# CTRL.net
KiCad netlist of a schematic drawn in Altium Designer
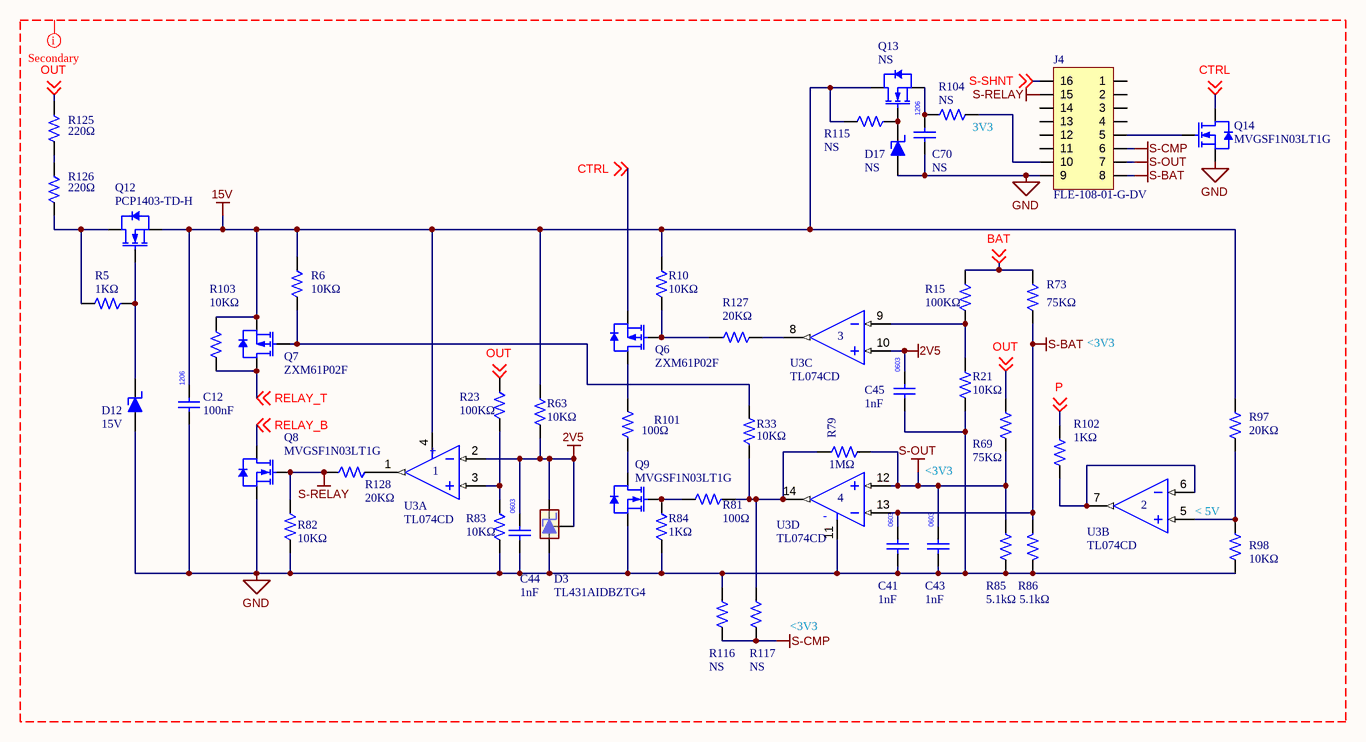
[diagram p0: CTRL.SchDoc]

(export (version "E")
  (design (tool "Eeschema 10.0.6"))
  (components
    (comp (ref "C12")
      (value "100nF")
      (footprint "CC/NM 1206")
      (libsource (lib "Capacitors_1206") (part "Capacitor 100nF"))
    )
    (comp (ref "C41")
      (value "1nF")
      (footprint "CC/NM 0603")
      (libsource (lib "Capacitors_0603") (part "Capacitor 1nF"))
    )
    (comp (ref "C43")
      (value "1nF")
      (footprint "CC/NM 0603")
      (libsource (lib "Capacitors_0603") (part "Capacitor 1nF"))
    )
    (comp (ref "C44")
      (value "1nF")
      (footprint "CC/NM 0603")
      (libsource (lib "Capacitors_0603") (part "Capacitor 1nF"))
    )
    (comp (ref "C45")
      (value "1nF")
      (footprint "CC/NM 0603")
      (libsource (lib "Capacitors_0603") (part "Capacitor 1nF"))
    )
    (comp (ref "C70")
      (value "NS")
      (footprint "CC/NM 1206")
      (description "100nF")
      (libsource (lib "Capacitors_1206") (part "Capacitor 100nF"))
    )
    (comp (ref "D3")
      (value "TL431AIDBZTG4")
      (footprint "SOT95P237X112-3N")
      (description "TL43xx Precision Programmable Reference")
      (libsource (lib "Charger") (part "TL431AIDBZTG4"))
    )
    (comp (ref "D12")
      (value "15V")
      (footprint "SOT95P237X112-3N")
      (libsource (lib "Charger") (part "Zener_18V"))
    )
    (comp (ref "D17")
      (value "NS")
      (footprint "SOT95P237X112-3N")
      (libsource (lib "Charger") (part "Zener_18V"))
    )
    (comp (ref "J4")
      (value "FLE-108-01-G-DV")
      (footprint "FLE-108-01-G-DV")
      (libsource (lib "Charger") (part "FLE-108-01-G-DV"))
    )
    (comp (ref "Q6")
      (value "ZXM61P02F")
      (footprint "SOT95P237X112-3N")
      (description "PMOS  -20V 0.9A 600 mohm")
      (libsource (lib "Charger") (part "ZXM61P02F"))
    )
    (comp (ref "Q7")
      (value "ZXM61P02F")
      (footprint "SOT95P237X112-3N")
      (description "PMOS  -20V 0.9A 600 mohm")
      (libsource (lib "Charger") (part "ZXM61P02F"))
    )
    (comp (ref "Q8")
      (value "MVGSF1N03LT1G")
      (footprint "SOT95P237X112-3N")
      (description "NMOS 30V 2.1A  80mR")
      (libsource (lib "Charger") (part "MVGSF1N03LT1G"))
    )
    (comp (ref "Q9")
      (value "MVGSF1N03LT1G")
      (footprint "SOT95P237X112-3N")
      (description "NMOS 30V 2.1A  80mR")
      (libsource (lib "Charger") (part "MVGSF1N03LT1G"))
    )
    (comp (ref "Q12")
      (value "PCP1403-TD-H")
      (footprint "SOT89/4")
      (description "NMOS 60V 4.5A 117mR")
      (libsource (lib "Charger") (part "PCP1403-TD-H"))
    )
    (comp (ref "Q13")
      (value "PCP1403-TD-H")
      (footprint "SOT89/4")
      (description "NMOS 60V 4.5A 117mR")
      (fields (field (name "MANUFACTURER PART NUMBER 1") "NS"))
      (libsource (lib "Charger") (part "PCP1403-TD-H"))
    )
    (comp (ref "Q14")
      (value "MVGSF1N03LT1G")
      (footprint "SOT95P237X112-3N")
      (description "NMOS 30V 2.1A  80mR")
      (libsource (lib "Charger") (part "MVGSF1N03LT1G"))
    )
    (comp (ref "R5")
      (value "1KΩ")
      (footprint "CC/NM 0603")
      (description "Resistor 0603")
      (libsource (lib "Resistors_0603") (part "Resistor 1K"))
    )
    (comp (ref "R6")
      (value "10KΩ")
      (footprint "CC/NM 0603")
      (description "Resistor 0603")
      (libsource (lib "Resistors_0603") (part "Resistor 10K"))
    )
    (comp (ref "R10")
      (value "10KΩ")
      (footprint "CC/NM 0603")
      (description "Resistor 0603")
      (libsource (lib "Resistors_0603") (part "Resistor 10K"))
    )
    (comp (ref "R15")
      (value "100KΩ")
      (footprint "CC/NM 0603")
      (description "Resistor 0603")
      (fields (field (name "Comment") "Resistor 100K"))
      (libsource (lib "Resistors_0603") (part "Resistor 100K"))
    )
    (comp (ref "R21")
      (value "10KΩ")
      (footprint "CC/NM 0603")
      (description "Resistor 0603")
      (libsource (lib "Resistors_0603") (part "Resistor 10K"))
    )
    (comp (ref "R23")
      (value "100KΩ")
      (footprint "CC/NM 0603")
      (description "Resistor 0603")
      (fields (field (name "Comment") "Resistor 100K"))
      (libsource (lib "Resistors_0603") (part "Resistor 100K"))
    )
    (comp (ref "R33")
      (value "10KΩ")
      (footprint "CC/NM 0603")
      (description "Resistor 0603")
      (fields (field (name "Comment") "Resistor 100"))
      (libsource (lib "Resistors_0603") (part "Resistor 100"))
    )
    (comp (ref "R63")
      (value "10KΩ")
      (footprint "CC/NM 0603")
      (description "Resistor 0603")
      (libsource (lib "Resistors_0603") (part "Resistor 10K"))
    )
    (comp (ref "R69")
      (value "75KΩ")
      (footprint "CC/NM 0603")
      (description "Resistor 0603")
      (fields (field (name "Comment") "Resistor 150K"))
      (libsource (lib "Resistors_0603") (part "Resistor 150K"))
    )
    (comp (ref "R73")
      (value "75KΩ")
      (footprint "CC/NM 0603")
      (description "Resistor 0603")
      (fields (field (name "Comment") "Resistor 150K"))
      (libsource (lib "Resistors_0603") (part "Resistor 150K"))
    )
    (comp (ref "R79")
      (value "1MΩ")
      (footprint "CC/NM 0603")
      (description "Resistor 0603")
      (fields (field (name "Comment") "Resistor 150K"))
      (libsource (lib "Resistors_0603") (part "Resistor 150K"))
    )
    (comp (ref "R81")
      (value "100Ω")
      (footprint "CC/NM 0603")
      (description "Resistor 0603")
      (fields (field (name "Comment") "Resistor 100"))
      (libsource (lib "Resistors_0603") (part "Resistor 100"))
    )
    (comp (ref "R82")
      (value "10KΩ")
      (footprint "CC/NM 0603")
      (description "Resistor 0603")
      (libsource (lib "Resistors_0603") (part "Resistor 10K"))
    )
    (comp (ref "R83")
      (value "10KΩ")
      (footprint "CC/NM 0603")
      (description "Resistor 0603")
      (libsource (lib "Resistors_0603") (part "Resistor 10K"))
    )
    (comp (ref "R84")
      (value "1KΩ")
      (footprint "CC/NM 0603")
      (description "Resistor 0603")
      (libsource (lib "Resistors_0603") (part "Resistor 10K"))
    )
    (comp (ref "R85")
      (value "5.1kΩ")
      (footprint "CC/NM 0603")
      (description "Resistor 0603")
      (libsource (lib "Resistors_0603") (part "Resistor 10K"))
    )
    (comp (ref "R86")
      (value "5.1kΩ")
      (footprint "CC/NM 0603")
      (description "Resistor 0603")
      (libsource (lib "Resistors_0603") (part "Resistor 10K"))
    )
    (comp (ref "R97")
      (value "20KΩ")
      (footprint "CC/NM 0603")
      (description "Resistor 0603")
      (fields (field (name "Comment") "Resistor 20K"))
      (libsource (lib "Resistors_0603") (part "Resistor 20K"))
    )
    (comp (ref "R98")
      (value "10KΩ")
      (footprint "CC/NM 0603")
      (description "Resistor 0603")
      (fields (field (name "Comment") "Resistor 10K"))
      (libsource (lib "Resistors_0603") (part "Resistor 10K"))
    )
    (comp (ref "R101")
      (value "100Ω")
      (footprint "CC/NM 0603")
      (description "Resistor 0603")
      (fields (field (name "Comment") "Resistor 100"))
      (libsource (lib "Resistors_0603") (part "Resistor 100"))
    )
    (comp (ref "R102")
      (value "1KΩ")
      (footprint "CC/NM 0603")
      (description "Resistor 0603")
      (libsource (lib "Resistors_0603") (part "Resistor 10K"))
    )
    (comp (ref "R103")
      (value "10KΩ")
      (footprint "CC/NM 0603")
      (description "Resistor 0603")
      (libsource (lib "Resistors_0603") (part "Resistor 10K"))
    )
    (comp (ref "R104")
      (value "NS")
      (footprint "CC/NM 0603")
      (description "Resistor 0603")
      (fields (field (name "Comment") "Resistor 1"))
      (libsource (lib "Resistors_0603") (part "Resistor 1"))
    )
    (comp (ref "R115")
      (value "NS")
      (footprint "CC/NM 0603")
      (description "Resistor 0603")
      (libsource (lib "Resistors_0603") (part "Resistor 1K"))
    )
    (comp (ref "R116")
      (value "NS")
      (footprint "CC/NM 0603")
      (description "Resistor 0603")
      (fields (field (name "Comment") "Resistor 8K2"))
      (libsource (lib "Resistors_0603") (part "Resistor 8K2"))
    )
    (comp (ref "R117")
      (value "NS")
      (footprint "CC/NM 0603")
      (description "Resistor 0603")
      (fields (field (name "Comment") "Resistor 30K"))
      (libsource (lib "Resistors_0603") (part "Resistor 30K"))
    )
    (comp (ref "R125")
      (value "220Ω")
      (footprint "CC/NM 1206")
      (description "Resistor 1206")
      (fields (field (name "Comment") "Resistor 220"))
      (libsource (lib "Resistors_1206") (part "Resistor 220"))
    )
    (comp (ref "R126")
      (value "220Ω")
      (footprint "CC/NM 1206")
      (description "Resistor 1206")
      (fields (field (name "Comment") "Resistor 220"))
      (libsource (lib "Resistors_1206") (part "Resistor 220"))
    )
    (comp (ref "R127")
      (value "20KΩ")
      (footprint "CC/NM 0603")
      (description "Resistor 0603")
      (libsource (lib "Resistors_0603") (part "Resistor 10K"))
    )
    (comp (ref "R128")
      (value "20KΩ")
      (footprint "CC/NM 0603")
      (description "Resistor 0603")
      (libsource (lib "Resistors_0603") (part "Resistor 1K"))
    )
    (comp (ref "U3")
      (value "TL074CD")
      (footprint "SOIC14")
      (description "3 MHz, 13 V/µs, 7V a 36V")
      (libsource (lib "Charger") (part "TL074CD"))
    )
  )
  (nets
    (net (code "1") (name "2V5") (class "Default")
      (node (ref "C44") (pin "1") (pinfunction "1_1") (pintype "passive"))
      (node (ref "C45") (pin "1") (pinfunction "1_1") (pintype "passive"))
      (node (ref "D3") (pin "1") (pinfunction "K_1") (pintype "passive"))
      (node (ref "D3") (pin "2") (pinfunction "REF_2") (pintype "passive"))
      (node (ref "R63") (pin "2") (pinfunction "2_2") (pintype "passive"))
      (node (ref "U3") (pin "10") (pinfunction "3IN+_10") (pintype "input"))
      (node (ref "U3") (pin "2") (pinfunction "1IN-_2") (pintype "input"))
    )
    (net (code "2") (name "15V") (class "Default")
      (node (ref "C12") (pin "1") (pinfunction "1_1") (pintype "passive"))
      (node (ref "Q12") (pin "2") (pinfunction "SOURCE_2") (pintype "passive"))
      (node (ref "Q13") (pin "3") (pinfunction "DRAIN_3") (pintype "passive"))
      (node (ref "Q7") (pin "2") (pinfunction "SOURCE_2") (pintype "passive"))
      (node (ref "R10") (pin "1") (pinfunction "1_1") (pintype "passive"))
      (node (ref "R103") (pin "1") (pinfunction "1_1") (pintype "passive"))
      (node (ref "R115") (pin "2") (pinfunction "2_2") (pintype "passive"))
      (node (ref "R6") (pin "1") (pinfunction "1_1") (pintype "passive"))
      (node (ref "R63") (pin "1") (pinfunction "1_1") (pintype "passive"))
      (node (ref "R97") (pin "1") (pinfunction "1_1") (pintype "passive"))
      (node (ref "U3") (pin "4") (pinfunction "VCC_4") (pintype "power_in"))
    )
    (net (code "3") (name "BAT") (class "Default")
      (node (ref "R15") (pin "1") (pinfunction "1_1") (pintype "passive"))
      (node (ref "R73") (pin "1") (pinfunction "1_1") (pintype "passive"))
    )
    (net (code "4") (name "CTRL") (class "Default")
      (node (ref "Q14") (pin "3") (pinfunction "DRAIN_3") (pintype "passive"))
      (node (ref "Q6") (pin "2") (pinfunction "SOURCE_2") (pintype "passive"))
    )
    (net (code "5") (name "GND") (class "Default")
      (node (ref "C12") (pin "2") (pinfunction "2_2") (pintype "passive"))
      (node (ref "C41") (pin "2") (pinfunction "2_2") (pintype "passive"))
      (node (ref "C43") (pin "2") (pinfunction "2_2") (pintype "passive"))
      (node (ref "C44") (pin "2") (pinfunction "2_2") (pintype "passive"))
      (node (ref "C45") (pin "2") (pinfunction "2_2") (pintype "passive"))
      (node (ref "C70") (pin "2") (pinfunction "2_2") (pintype "passive"))
      (node (ref "D12") (pin "1") (pinfunction "A_1") (pintype "passive"))
      (node (ref "D17") (pin "1") (pinfunction "A_1") (pintype "passive"))
      (node (ref "D3") (pin "3") (pinfunction "A_3") (pintype "passive"))
      (node (ref "J4") (pin "9") (pinfunction "9_9") (pintype "passive"))
      (node (ref "Q14") (pin "2") (pinfunction "SOURCE_2") (pintype "passive"))
      (node (ref "Q8") (pin "2") (pinfunction "SOURCE_2") (pintype "passive"))
      (node (ref "Q9") (pin "2") (pinfunction "SOURCE_2") (pintype "passive"))
      (node (ref "R116") (pin "1") (pinfunction "1_1") (pintype "passive"))
      (node (ref "R21") (pin "2") (pinfunction "2_2") (pintype "passive"))
      (node (ref "R82") (pin "2") (pinfunction "2_2") (pintype "passive"))
      (node (ref "R83") (pin "2") (pinfunction "2_2") (pintype "passive"))
      (node (ref "R84") (pin "2") (pinfunction "2_2") (pintype "passive"))
      (node (ref "R85") (pin "2") (pinfunction "2_2") (pintype "passive"))
      (node (ref "R86") (pin "2") (pinfunction "2_2") (pintype "passive"))
      (node (ref "R98") (pin "2") (pinfunction "2_2") (pintype "passive"))
      (node (ref "U3") (pin "11") (pinfunction "-VCC_11") (pintype "power_in"))
    )
    (net (code "6") (name "Net-(D12-K)") (class "Default")
      (node (ref "D12") (pin "3") (pinfunction "K_3") (pintype "passive"))
      (node (ref "Q12") (pin "1") (pinfunction "GATE_1") (pintype "passive"))
      (node (ref "R5") (pin "1") (pinfunction "1_1") (pintype "passive"))
    )
    (net (code "7") (name "Net-(D17-K)") (class "Default")
      (node (ref "D17") (pin "3") (pinfunction "K_3") (pintype "passive"))
      (node (ref "Q13") (pin "1") (pinfunction "GATE_1") (pintype "passive"))
      (node (ref "R115") (pin "1") (pinfunction "1_1") (pintype "passive"))
    )
    (net (code "8") (name "Net-(J4-Pad10)") (class "Default")
      (node (ref "J4") (pin "10") (pinfunction "10_10") (pintype "passive"))
      (node (ref "R104") (pin "2") (pinfunction "2_2") (pintype "passive"))
    )
    (net (code "9") (name "Net-(Q6-DRAIN)") (class "Default")
      (node (ref "Q6") (pin "3") (pinfunction "DRAIN_3") (pintype "passive"))
      (node (ref "R101") (pin "2") (pinfunction "2_2") (pintype "passive"))
    )
    (net (code "10") (name "Net-(Q6-GATE)") (class "Default")
      (node (ref "Q6") (pin "1") (pinfunction "GATE_1") (pintype "passive"))
      (node (ref "R10") (pin "2") (pinfunction "2_2") (pintype "passive"))
      (node (ref "R127") (pin "1") (pinfunction "1_1") (pintype "passive"))
    )
    (net (code "11") (name "Net-(Q7-GATE)") (class "Default")
      (node (ref "Q7") (pin "1") (pinfunction "GATE_1") (pintype "passive"))
      (node (ref "R33") (pin "2") (pinfunction "2_2") (pintype "passive"))
      (node (ref "R6") (pin "2") (pinfunction "2_2") (pintype "passive"))
    )
    (net (code "12") (name "Net-(Q9-DRAIN)") (class "Default")
      (node (ref "Q9") (pin "3") (pinfunction "DRAIN_3") (pintype "passive"))
      (node (ref "R101") (pin "1") (pinfunction "1_1") (pintype "passive"))
    )
    (net (code "13") (name "Net-(Q9-GATE)") (class "Default")
      (node (ref "Q9") (pin "1") (pinfunction "GATE_1") (pintype "passive"))
      (node (ref "R81") (pin "2") (pinfunction "2_2") (pintype "passive"))
      (node (ref "R84") (pin "1") (pinfunction "1_1") (pintype "passive"))
    )
    (net (code "14") (name "Net-(Q12-DRAIN)") (class "Default")
      (node (ref "Q12") (pin "3") (pinfunction "DRAIN_3") (pintype "passive"))
      (node (ref "R126") (pin "2") (pinfunction "2_2") (pintype "passive"))
      (node (ref "R5") (pin "2") (pinfunction "2_2") (pintype "passive"))
    )
    (net (code "15") (name "Net-(Q13-SOURCE)") (class "Default")
      (node (ref "C70") (pin "1") (pinfunction "1_1") (pintype "passive"))
      (node (ref "Q13") (pin "2") (pinfunction "SOURCE_2") (pintype "passive"))
      (node (ref "R104") (pin "1") (pinfunction "1_1") (pintype "passive"))
    )
    (net (code "16") (name "Net-(Q14-GATE)") (class "Default")
      (node (ref "J4") (pin "5") (pinfunction "5_5") (pintype "passive"))
      (node (ref "Q14") (pin "1") (pinfunction "GATE_1") (pintype "passive"))
    )
    (net (code "17") (name "Net-(R125-Pad2)") (class "Default")
      (node (ref "R125") (pin "2") (pinfunction "2_2") (pintype "passive"))
      (node (ref "R126") (pin "1") (pinfunction "1_1") (pintype "passive"))
    )
    (net (code "18") (name "Net-(U3A-1IN+)") (class "Default")
      (node (ref "R23") (pin "2") (pinfunction "2_2") (pintype "passive"))
      (node (ref "R83") (pin "1") (pinfunction "1_1") (pintype "passive"))
      (node (ref "U3") (pin "3") (pinfunction "1IN+_3") (pintype "input"))
    )
    (net (code "19") (name "Net-(U3A-1OUT)") (class "Default")
      (node (ref "R128") (pin "2") (pinfunction "2_2") (pintype "passive"))
      (node (ref "U3") (pin "1") (pinfunction "1OUT_1") (pintype "output"))
    )
    (net (code "20") (name "Net-(U3B-2IN+)") (class "Default")
      (node (ref "R97") (pin "2") (pinfunction "2_2") (pintype "passive"))
      (node (ref "R98") (pin "1") (pinfunction "1_1") (pintype "passive"))
      (node (ref "U3") (pin "5") (pinfunction "2IN+_5") (pintype "input"))
    )
    (net (code "21") (name "Net-(U3B-2IN-)") (class "Default")
      (node (ref "R102") (pin "2") (pinfunction "2_2") (pintype "passive"))
      (node (ref "U3") (pin "6") (pinfunction "2IN-_6") (pintype "input"))
      (node (ref "U3") (pin "7") (pinfunction "2OUT_7") (pintype "output"))
    )
    (net (code "22") (name "Net-(U3C-3IN-)") (class "Default")
      (node (ref "R15") (pin "2") (pinfunction "2_2") (pintype "passive"))
      (node (ref "R21") (pin "1") (pinfunction "1_1") (pintype "passive"))
      (node (ref "U3") (pin "9") (pinfunction "3IN-_9") (pintype "input"))
    )
    (net (code "23") (name "Net-(U3C-3OUT)") (class "Default")
      (node (ref "R127") (pin "2") (pinfunction "2_2") (pintype "passive"))
      (node (ref "U3") (pin "8") (pinfunction "3OUT_8") (pintype "output"))
    )
    (net (code "24") (name "Net-(U3D-4OUT)") (class "Default")
      (node (ref "R117") (pin "1") (pinfunction "1_1") (pintype "passive"))
      (node (ref "R33") (pin "1") (pinfunction "1_1") (pintype "passive"))
      (node (ref "R79") (pin "1") (pinfunction "1_1") (pintype "passive"))
      (node (ref "R81") (pin "1") (pinfunction "1_1") (pintype "passive"))
      (node (ref "U3") (pin "14") (pinfunction "4OUT_14") (pintype "output"))
    )
    (net (code "25") (name "OUT") (class "Default")
      (node (ref "R125") (pin "1") (pinfunction "1_1") (pintype "passive"))
      (node (ref "R23") (pin "1") (pinfunction "1_1") (pintype "passive"))
      (node (ref "R69") (pin "1") (pinfunction "1_1") (pintype "passive"))
    )
    (net (code "26") (name "P") (class "Default")
      (node (ref "R102") (pin "1") (pinfunction "1_1") (pintype "passive"))
    )
    (net (code "27") (name "RELAY_B") (class "Default")
      (node (ref "Q8") (pin "3") (pinfunction "DRAIN_3") (pintype "passive"))
    )
    (net (code "28") (name "RELAY_T") (class "Default")
      (node (ref "Q7") (pin "3") (pinfunction "DRAIN_3") (pintype "passive"))
      (node (ref "R103") (pin "2") (pinfunction "2_2") (pintype "passive"))
    )
    (net (code "29") (name "S-BAT") (class "Default")
      (node (ref "C41") (pin "1") (pinfunction "1_1") (pintype "passive"))
      (node (ref "J4") (pin "8") (pinfunction "8_8") (pintype "passive"))
      (node (ref "R73") (pin "2") (pinfunction "2_2") (pintype "passive"))
      (node (ref "R86") (pin "1") (pinfunction "1_1") (pintype "passive"))
      (node (ref "U3") (pin "13") (pinfunction "4IN-_13") (pintype "input"))
    )
    (net (code "30") (name "S-CMP") (class "Default")
      (node (ref "J4") (pin "6") (pinfunction "6_6") (pintype "passive"))
      (node (ref "R116") (pin "2") (pinfunction "2_2") (pintype "passive"))
      (node (ref "R117") (pin "2") (pinfunction "2_2") (pintype "passive"))
    )
    (net (code "31") (name "S-OUT") (class "Default")
      (node (ref "C43") (pin "1") (pinfunction "1_1") (pintype "passive"))
      (node (ref "J4") (pin "7") (pinfunction "7_7") (pintype "passive"))
      (node (ref "R69") (pin "2") (pinfunction "2_2") (pintype "passive"))
      (node (ref "R79") (pin "2") (pinfunction "2_2") (pintype "passive"))
      (node (ref "R85") (pin "1") (pinfunction "1_1") (pintype "passive"))
      (node (ref "U3") (pin "12") (pinfunction "4IN+_12") (pintype "input"))
    )
    (net (code "32") (name "S-RELAY") (class "Default")
      (node (ref "J4") (pin "15") (pinfunction "15_15") (pintype "passive"))
      (node (ref "Q8") (pin "1") (pinfunction "GATE_1") (pintype "passive"))
      (node (ref "R128") (pin "1") (pinfunction "1_1") (pintype "passive"))
      (node (ref "R82") (pin "1") (pinfunction "1_1") (pintype "passive"))
    )
    (net (code "33") (name "S-SHNT") (class "Default")
      (node (ref "J4") (pin "16") (pinfunction "16_16") (pintype "passive"))
    )
    (net (code "34") (name "unconnected-(J4-Pad1)") (class "Default")
      (node (ref "J4") (pin "1") (pinfunction "1_1") (pintype "passive"))
    )
    (net (code "35") (name "unconnected-(J4-Pad2)") (class "Default")
      (node (ref "J4") (pin "2") (pinfunction "2_2") (pintype "passive"))
    )
    (net (code "36") (name "unconnected-(J4-Pad3)") (class "Default")
      (node (ref "J4") (pin "3") (pinfunction "3_3") (pintype "passive"))
    )
    (net (code "37") (name "unconnected-(J4-Pad4)") (class "Default")
      (node (ref "J4") (pin "4") (pinfunction "4_4") (pintype "passive"))
    )
    (net (code "38") (name "unconnected-(J4-Pad11)") (class "Default")
      (node (ref "J4") (pin "11") (pinfunction "11_11") (pintype "passive"))
    )
    (net (code "39") (name "unconnected-(J4-Pad12)") (class "Default")
      (node (ref "J4") (pin "12") (pinfunction "12_12") (pintype "passive"))
    )
    (net (code "40") (name "unconnected-(J4-Pad13)") (class "Default")
      (node (ref "J4") (pin "13") (pinfunction "13_13") (pintype "passive"))
    )
    (net (code "41") (name "unconnected-(J4-Pad14)") (class "Default")
      (node (ref "J4") (pin "14") (pinfunction "14_14") (pintype "passive"))
    )
  )
)
